# DM1098LUXD-LITE_IMU.net
KiCad netlist of a schematic drawn in Altium Designer
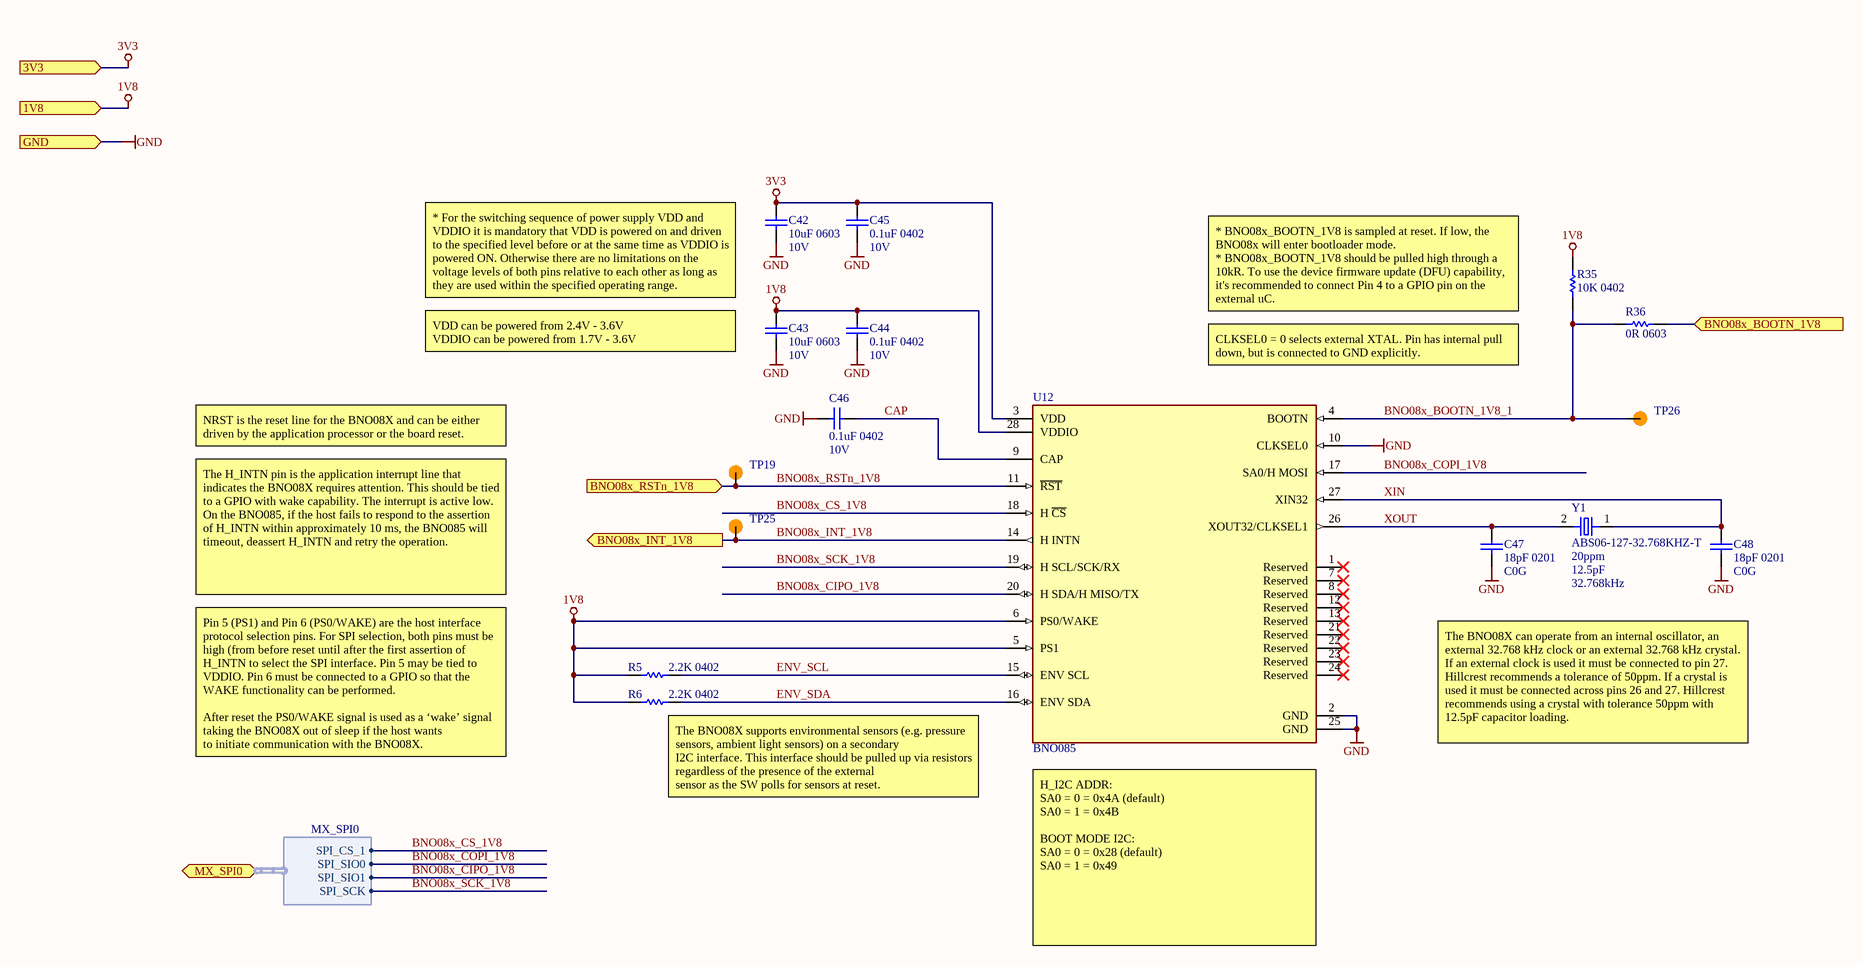
[diagram p0: DM1098LUXD-LITE_IMU.SchDoc]

(export (version "E")
  (design (tool "Eeschema 10.0.6"))
  (components
    (comp (ref "C42")
      (value "10uF 0603")
      (footprint "CAP_Altium_Vault_Generic:CAPC0603(1608)100_L")
      (description "CAP CER 10UF 10V X5R 0603 20%")
      (fields (field (name "TOLERANCE") "20%") (field (name "VOLTAGE RATING") "10V"))
      (libsource (lib "LuxonisMaster") (part "GRM188R61A106ME69D"))
    )
    (comp (ref "C43")
      (value "10uF 0603")
      (footprint "CAP_Altium_Vault_Generic:CAPC0603(1608)100_L")
      (description "CAP CER 10UF 10V X5R 0603 20%")
      (fields (field (name "TOLERANCE") "20%") (field (name "VOLTAGE RATING") "10V"))
      (libsource (lib "LuxonisMaster") (part "GRM188R61A106ME69D"))
    )
    (comp (ref "C44")
      (value "0.1uF 0402")
      (footprint "CAP_Altium_Vault_Generic:CAPC0402(1005)70_L")
      (description "CAP CER 0.1UF 10V X7R 0402 5%")
      (fields (field (name "TOLERANCE") "5%") (field (name "VOLTAGE RATING") "10V"))
      (libsource (lib "LuxonisMaster") (part "GRM155R71A104JA01D"))
    )
    (comp (ref "C45")
      (value "0.1uF 0402")
      (footprint "CAP_Altium_Vault_Generic:CAPC0402(1005)70_L")
      (description "CAP CER 0.1UF 10V X7R 0402 5%")
      (fields (field (name "TOLERANCE") "5%") (field (name "VOLTAGE RATING") "10V"))
      (libsource (lib "LuxonisMaster") (part "GRM155R71A104JA01D"))
    )
    (comp (ref "C46")
      (value "0.1uF 0402")
      (footprint "CAP_Altium_Vault_Generic:CAPC0402(1005)70_L")
      (description "CAP CER 0.1UF 10V X7R 0402 5%")
      (fields (field (name "TOLERANCE") "5%") (field (name "VOLTAGE RATING") "10V"))
      (libsource (lib "LuxonisMaster") (part "GRM155R71A104JA01D"))
    )
    (comp (ref "C47")
      (value "18pF 0201")
      (footprint "CAPC0201(0603)33_L")
      (description "Cap Ceramic 18pF 25V C0G 1% Pad SMD 0201 125C T/R")
      (fields (field (name "TOLERANCE") "1%") (field (name "DIELECTRIC") "C0G"))
      (libsource (lib "LuxonisMaster") (part "GRM0335C1E180FA01D"))
    )
    (comp (ref "C48")
      (value "18pF 0201")
      (footprint "CAPC0201(0603)33_L")
      (description "Cap Ceramic 18pF 25V C0G 1% Pad SMD 0201 125C T/R")
      (fields (field (name "TOLERANCE") "1%") (field (name "DIELECTRIC") "C0G"))
      (libsource (lib "LuxonisMaster") (part "GRM0335C1E180FA01D"))
    )
    (comp (ref "R5")
      (value "2.2K 0402")
      (footprint "RES_Altium_Vault_Generic:RESC0402(1005)_L")
      (description "RES SMD 2.2K OHM 1% 1/16W 0402")
      (fields (field (name "TOLERANCE") "1%"))
      (libsource (lib "LuxonisMaster") (part "RC0402FR-072K2L"))
    )
    (comp (ref "R6")
      (value "2.2K 0402")
      (footprint "RES_Altium_Vault_Generic:RESC0402(1005)_L")
      (description "RES SMD 2.2K OHM 1% 1/16W 0402")
      (fields (field (name "TOLERANCE") "1%"))
      (libsource (lib "LuxonisMaster") (part "RC0402FR-072K2L"))
    )
    (comp (ref "R35")
      (value "10K 0402")
      (footprint "RES_Altium_Vault_Generic:RESC0402(1005)_L")
      (fields (field (name "TOLERANCE") "1%"))
      (libsource (lib "LuxonisMaster") (part "RC0402FR-1310KL"))
    )
    (comp (ref "R36")
      (value "0R 0603")
      (footprint "RES_Altium_Vault_Generic:RESC0603(1608)_L")
      (fields (field (name "TOLERANCE") "5%"))
      (libsource (lib "LuxonisMaster") (part "CRCW06030000Z0EA"))
    )
    (comp (ref "TP19")
      (value "TP100_200_NS")
      (footprint "LuxonisMaster:TP100_200_NS")
      (libsource (lib "LuxonisMaster") (part "TEST_POINT"))
    )
    (comp (ref "TP25")
      (value "TP100_200_NS")
      (footprint "LuxonisMaster:TP100_200_NS")
      (libsource (lib "LuxonisMaster") (part "TEST_POINT"))
    )
    (comp (ref "TP26")
      (value "TP100_200_NS")
      (footprint "LuxonisMaster:TP100_200_NS")
      (libsource (lib "LuxonisMaster") (part "TEST_POINT"))
    )
    (comp (ref "U12")
      (value "BNO085")
      (footprint "BNO085")
      (description "IMU ACCEL/GYRO/MAG I2C 32BIT")
      (libsource (lib "LuxonisMaster") (part "BNO085"))
    )
    (comp (ref "Y1")
      (value "ABS06-127-32.768KHZ-T")
      (footprint "ABS06-127-32.768KHZ-T")
      (description "CRYSTAL 32.768kHz ±20ppm Crystal 12.5pF 90 kOhms 2-SMD, No Lead")
      (fields
        (field (name "FREQUENCY TOLERANCE") "20ppm")
        (field (name "LOAD CAPACITANCE") "12.5pF")
        (field (name "FREQUENCY") "32.768kHz")
      )
      (libsource (lib "LuxonisMaster") (part "ABS06-127-32.768KHZ-T"))
    )
  )
  (nets
    (net (code "2") (name "/BNO08x_BOOTN_1V8") (class "Default")
      (node (ref "R36") (pin "2") (pinfunction "2_2") (pintype "passive"))
    )
    (net (code "3") (name "/BNO08x_BOOTN_1V8_1") (class "Default")
      (node (ref "R35") (pin "1") (pinfunction "1_1") (pintype "passive"))
      (node (ref "R36") (pin "1") (pinfunction "1_1") (pintype "passive"))
      (node (ref "TP26") (pin "1") (pintype "passive"))
      (node (ref "U12") (pin "4") (pinfunction "BOOTN_4") (pintype "input"))
    )
    (net (code "4") (name "/BNO08x_CIPO_1V8") (class "Default")
      (node (ref "U12") (pin "20") (pinfunction "H_SDA/H_MISO/TX_20") (pintype "bidirectional"))
    )
    (net (code "5") (name "/BNO08x_COPI_1V8") (class "Default")
      (node (ref "U12") (pin "17") (pinfunction "SA0/H_MOSI_17") (pintype "input"))
    )
    (net (code "6") (name "/BNO08x_CS_1V8") (class "Default")
      (node (ref "U12") (pin "18") (pinfunction "H_~{CS}_18") (pintype "input"))
    )
    (net (code "7") (name "/BNO08x_INT_1V8") (class "Default")
      (node (ref "TP25") (pin "1") (pintype "passive"))
      (node (ref "U12") (pin "14") (pinfunction "H_INTN_14") (pintype "output"))
    )
    (net (code "8") (name "/BNO08x_RSTn_1V8") (class "Default")
      (node (ref "TP19") (pin "1") (pintype "passive"))
      (node (ref "U12") (pin "11") (pinfunction "~{RST}_11") (pintype "input"))
    )
    (net (code "9") (name "/BNO08x_SCK_1V8") (class "Default")
      (node (ref "U12") (pin "19") (pinfunction "H_SCL/SCK/RX_19") (pintype "bidirectional"))
    )
    (net (code "10") (name "/CAP") (class "Default")
      (node (ref "C46") (pin "1") (pinfunction "1_1") (pintype "passive"))
      (node (ref "U12") (pin "9") (pinfunction "CAP_9") (pintype "passive"))
    )
    (net (code "11") (name "/ENV_SCL") (class "Default")
      (node (ref "R5") (pin "2") (pinfunction "2_2") (pintype "passive"))
      (node (ref "U12") (pin "15") (pinfunction "ENV_SCL_15") (pintype "bidirectional"))
    )
    (net (code "12") (name "/ENV_SDA") (class "Default")
      (node (ref "R6") (pin "2") (pinfunction "2_2") (pintype "passive"))
      (node (ref "U12") (pin "16") (pinfunction "ENV_SDA_16") (pintype "bidirectional"))
    )
    (net (code "13") (name "/XIN") (class "Default")
      (node (ref "C48") (pin "2") (pinfunction "2_2") (pintype "passive"))
      (node (ref "U12") (pin "27") (pinfunction "XIN32_27") (pintype "input"))
      (node (ref "Y1") (pin "1") (pinfunction "1_1") (pintype "passive"))
    )
    (net (code "14") (name "/XOUT") (class "Default")
      (node (ref "C47") (pin "2") (pinfunction "2_2") (pintype "passive"))
      (node (ref "U12") (pin "26") (pinfunction "XOUT32/CLKSEL1_26") (pintype "output"))
      (node (ref "Y1") (pin "2") (pinfunction "2_2") (pintype "passive"))
    )
    (net (code "16") (name "1V8") (class "Default")
      (node (ref "C43") (pin "2") (pinfunction "2_2") (pintype "passive"))
      (node (ref "C44") (pin "2") (pinfunction "2_2") (pintype "passive"))
      (node (ref "R35") (pin "2") (pinfunction "2_2") (pintype "passive"))
      (node (ref "R5") (pin "1") (pinfunction "1_1") (pintype "passive"))
      (node (ref "R6") (pin "1") (pinfunction "1_1") (pintype "passive"))
      (node (ref "U12") (pin "28") (pinfunction "VDDIO_28") (pintype "power_in"))
      (node (ref "U12") (pin "5") (pinfunction "PS1_5") (pintype "input"))
      (node (ref "U12") (pin "6") (pinfunction "PS0/WAKE_6") (pintype "input"))
    )
    (net (code "17") (name "3V3") (class "Default")
      (node (ref "C42") (pin "2") (pinfunction "2_2") (pintype "passive"))
      (node (ref "C45") (pin "2") (pinfunction "2_2") (pintype "passive"))
      (node (ref "U12") (pin "3") (pinfunction "VDD_3") (pintype "power_in"))
    )
    (net (code "18") (name "GND") (class "Default")
      (node (ref "C42") (pin "1") (pinfunction "1_1") (pintype "passive"))
      (node (ref "C43") (pin "1") (pinfunction "1_1") (pintype "passive"))
      (node (ref "C44") (pin "1") (pinfunction "1_1") (pintype "passive"))
      (node (ref "C45") (pin "1") (pinfunction "1_1") (pintype "passive"))
      (node (ref "C46") (pin "2") (pinfunction "2_2") (pintype "passive"))
      (node (ref "C47") (pin "1") (pinfunction "1_1") (pintype "passive"))
      (node (ref "C48") (pin "1") (pinfunction "1_1") (pintype "passive"))
      (node (ref "U12") (pin "10") (pinfunction "CLKSEL0_10") (pintype "input"))
      (node (ref "U12") (pin "2") (pinfunction "GND_2") (pintype "power_in"))
      (node (ref "U12") (pin "25") (pinfunction "GND_25") (pintype "power_in"))
    )
    (net (code "19") (name "unconnected-(U12-Reserved-Pad1)") (class "Default")
      (node (ref "U12") (pin "1") (pinfunction "Reserved_1") (pintype "passive+no_connect"))
    )
    (net (code "20") (name "unconnected-(U12-Reserved-Pad7)") (class "Default")
      (node (ref "U12") (pin "7") (pinfunction "Reserved_7") (pintype "passive+no_connect"))
    )
    (net (code "21") (name "unconnected-(U12-Reserved-Pad8)") (class "Default")
      (node (ref "U12") (pin "8") (pinfunction "Reserved_8") (pintype "passive+no_connect"))
    )
    (net (code "22") (name "unconnected-(U12-Reserved-Pad12)") (class "Default")
      (node (ref "U12") (pin "12") (pinfunction "Reserved_12") (pintype "passive+no_connect"))
    )
    (net (code "23") (name "unconnected-(U12-Reserved-Pad13)") (class "Default")
      (node (ref "U12") (pin "13") (pinfunction "Reserved_13") (pintype "passive+no_connect"))
    )
    (net (code "24") (name "unconnected-(U12-Reserved-Pad21)") (class "Default")
      (node (ref "U12") (pin "21") (pinfunction "Reserved_21") (pintype "passive+no_connect"))
    )
    (net (code "25") (name "unconnected-(U12-Reserved-Pad22)") (class "Default")
      (node (ref "U12") (pin "22") (pinfunction "Reserved_22") (pintype "passive+no_connect"))
    )
    (net (code "26") (name "unconnected-(U12-Reserved-Pad23)") (class "Default")
      (node (ref "U12") (pin "23") (pinfunction "Reserved_23") (pintype "passive+no_connect"))
    )
    (net (code "27") (name "unconnected-(U12-Reserved-Pad24)") (class "Default")
      (node (ref "U12") (pin "24") (pinfunction "Reserved_24") (pintype "passive+no_connect"))
    )
  )
)
